# CommsBoard.net
KiCad netlist of a schematic drawn in EAGLE
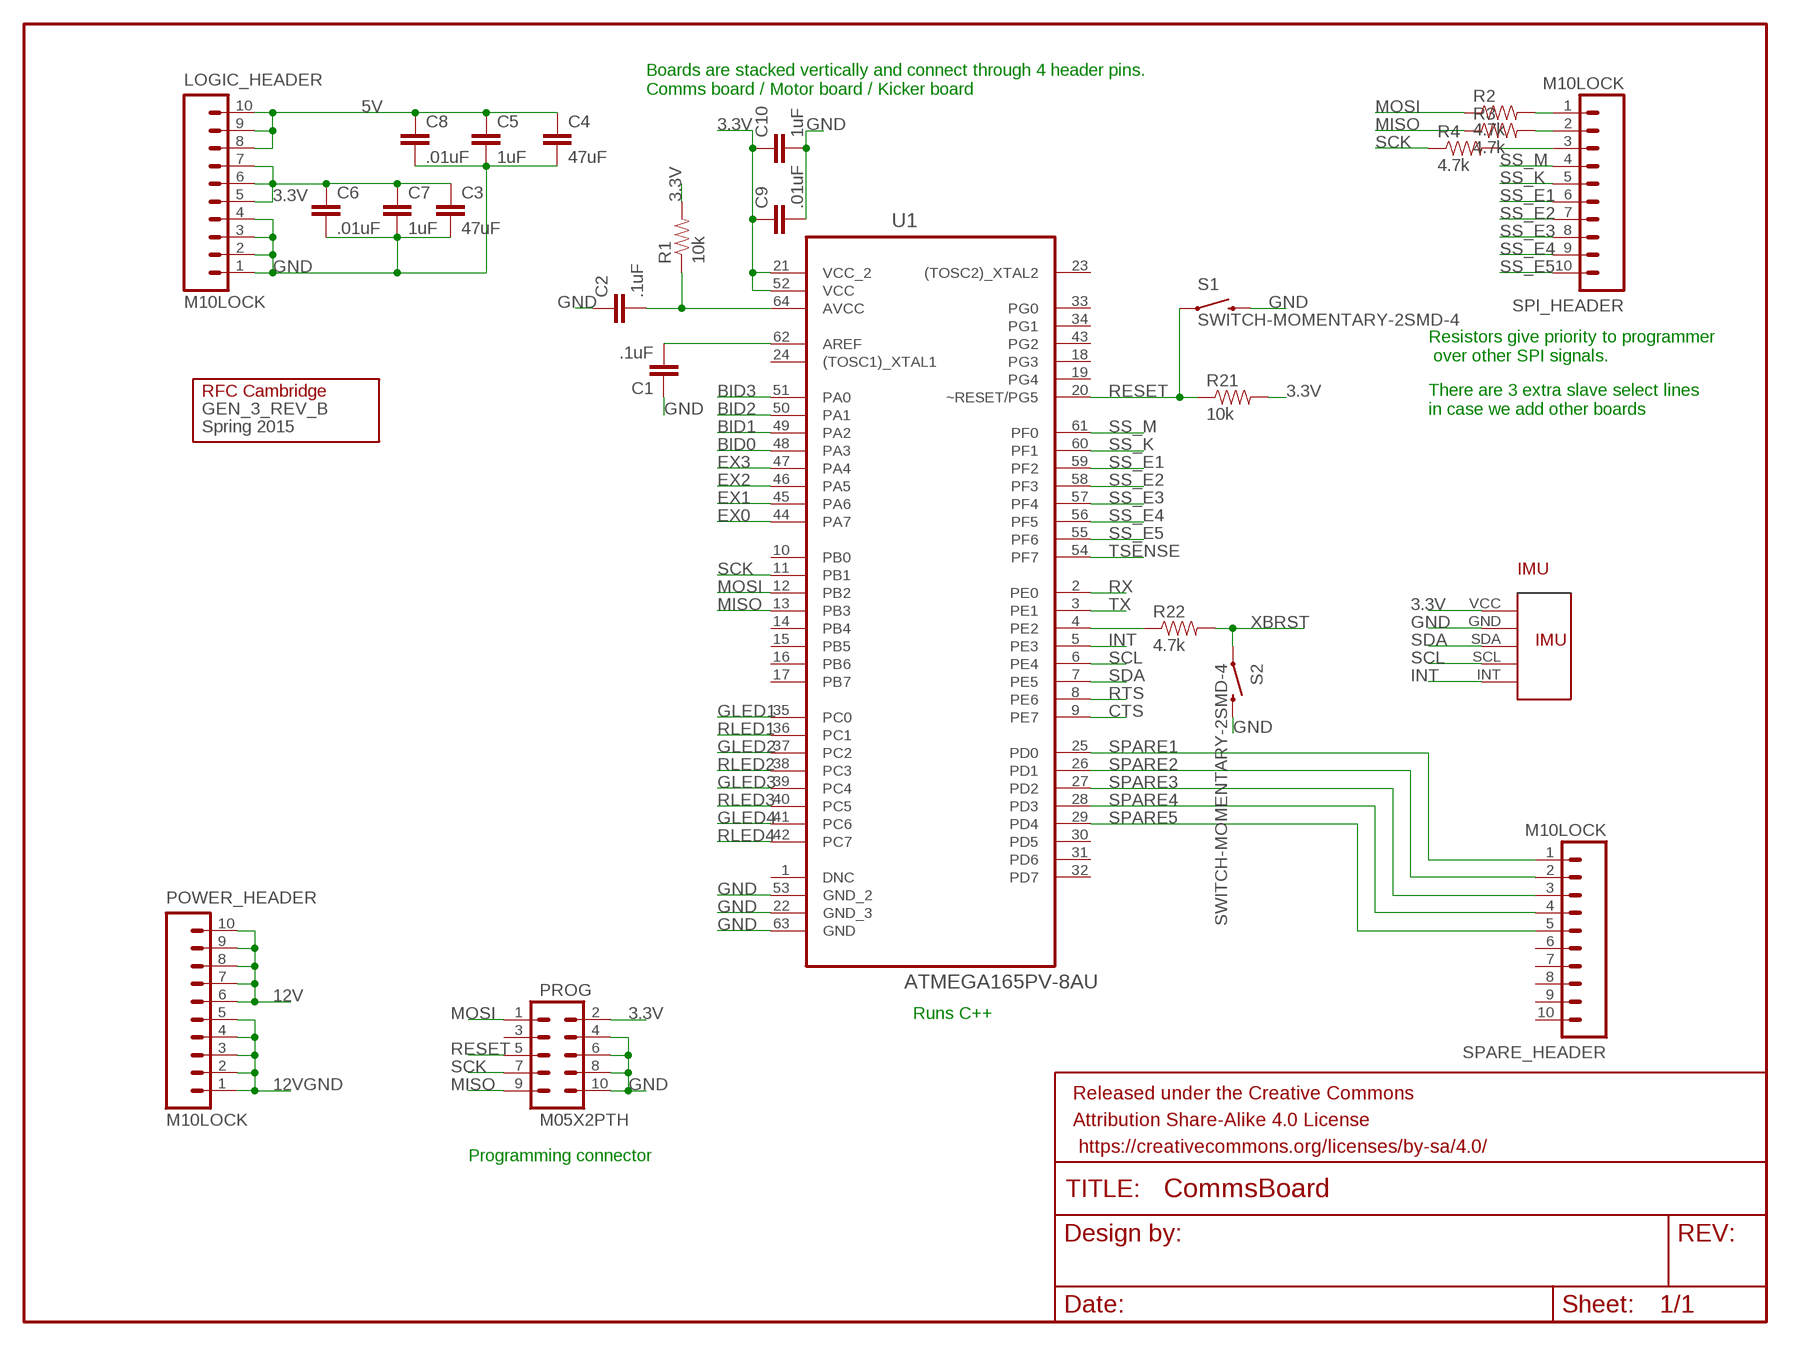
[diagram p0: schematic, sheet 1, part 1 of 2]
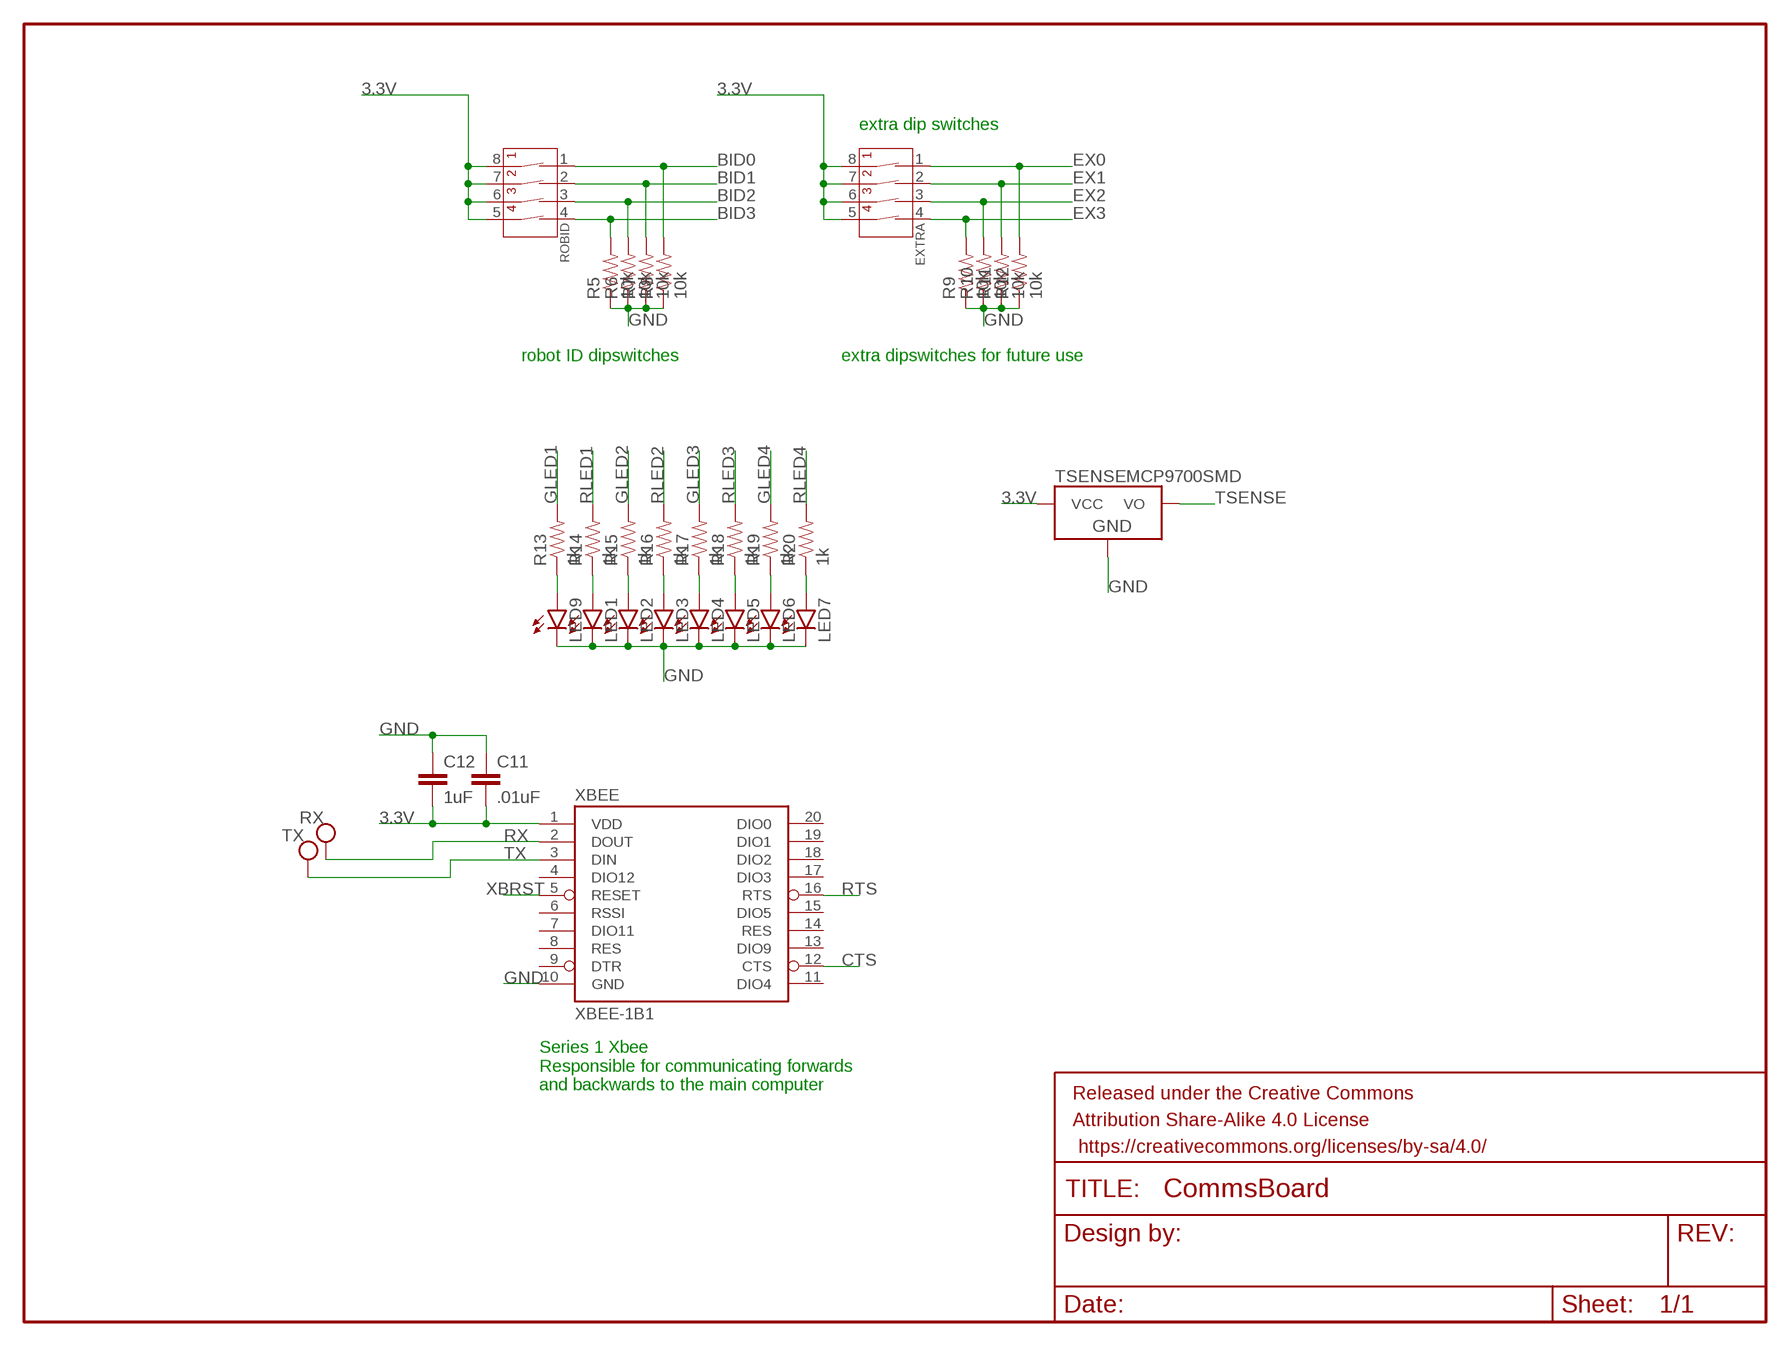
[diagram p1: schematic, sheet 1, part 2 of 2]

(export (version "E")
  (design (tool "Eeschema 10.0.6"))
  (components
    (comp (ref "C1")
      (value ".1uF")
      (footprint "eagle-import:0805")
      (libsource (lib "eagle-import") (part "CAP0805"))
    )
    (comp (ref "C2")
      (value ".1uF")
      (footprint "eagle-import:0805")
      (libsource (lib "eagle-import") (part "CAP0805"))
    )
    (comp (ref "C3")
      (value "47uF")
      (footprint "eagle-import:1206")
      (libsource (lib "eagle-import") (part "CAP1206"))
    )
    (comp (ref "C4")
      (value "47uF")
      (footprint "eagle-import:1206")
      (libsource (lib "eagle-import") (part "CAP1206"))
    )
    (comp (ref "C5")
      (value "1uF")
      (footprint "eagle-import:0805")
      (libsource (lib "eagle-import") (part "CAP0805"))
    )
    (comp (ref "C6")
      (value ".01uF")
      (footprint "eagle-import:0805")
      (libsource (lib "eagle-import") (part "CAP0805"))
    )
    (comp (ref "C7")
      (value "1uF")
      (footprint "eagle-import:0805")
      (libsource (lib "eagle-import") (part "CAP0805"))
    )
    (comp (ref "C8")
      (value ".01uF")
      (footprint "eagle-import:0805")
      (libsource (lib "eagle-import") (part "CAP0805"))
    )
    (comp (ref "C9")
      (value ".01uF")
      (footprint "eagle-import:0805")
      (libsource (lib "eagle-import") (part "CAP0805"))
    )
    (comp (ref "C10")
      (value "1uF")
      (footprint "eagle-import:0805")
      (libsource (lib "eagle-import") (part "CAP0805"))
    )
    (comp (ref "C11")
      (value ".01uF")
      (footprint "eagle-import:0805")
      (libsource (lib "eagle-import") (part "CAP0805"))
    )
    (comp (ref "C12")
      (value "1uF")
      (footprint "eagle-import:0805")
      (libsource (lib "eagle-import") (part "CAP0805"))
    )
    (comp (ref "EXTRA")
      (value "4-POS-DIP")
      (footprint "eagle-import:4-POS-DIP-SMD")
      (libsource (lib "eagle-import") (part "4-POS-DIP"))
    )
    (comp (ref "FRAME1")
      (value "FRAME-LETTER")
      (footprint "eagle-import:CREATIVE_COMMONS")
      (libsource (lib "eagle-import") (part "FRAME-LETTER"))
    )
    (comp (ref "FRAME2")
      (value "FRAME-LETTER")
      (footprint "eagle-import:CREATIVE_COMMONS")
      (libsource (lib "eagle-import") (part "FRAME-LETTER"))
    )
    (comp (ref "GEN_3_REV_B")
      (value "Spring 2015")
      (footprint "eagle-import:LOGO")
      (libsource (lib "eagle-import") (part "LOGO"))
    )
    (comp (ref "IMU")
      (value "MPU6050IMUMPU")
      (footprint "eagle-import:MPU-6050IMU")
      (libsource (lib "eagle-import") (part "MPU6050IMUMPU"))
    )
    (comp (ref "LED1")
      (value "LED1206")
      (footprint "eagle-import:LED-1206")
      (libsource (lib "eagle-import") (part "LED1206"))
    )
    (comp (ref "LED2")
      (value "LED1206")
      (footprint "eagle-import:LED-1206")
      (libsource (lib "eagle-import") (part "LED1206"))
    )
    (comp (ref "LED3")
      (value "LED1206")
      (footprint "eagle-import:LED-1206")
      (libsource (lib "eagle-import") (part "LED1206"))
    )
    (comp (ref "LED4")
      (value "LED1206")
      (footprint "eagle-import:LED-1206")
      (libsource (lib "eagle-import") (part "LED1206"))
    )
    (comp (ref "LED5")
      (value "LED1206")
      (footprint "eagle-import:LED-1206")
      (libsource (lib "eagle-import") (part "LED1206"))
    )
    (comp (ref "LED6")
      (value "LED1206")
      (footprint "eagle-import:LED-1206")
      (libsource (lib "eagle-import") (part "LED1206"))
    )
    (comp (ref "LED7")
      (value "LED1206")
      (footprint "eagle-import:LED-1206")
      (libsource (lib "eagle-import") (part "LED1206"))
    )
    (comp (ref "LED9")
      (value "LED1206")
      (footprint "eagle-import:LED-1206")
      (libsource (lib "eagle-import") (part "LED1206"))
    )
    (comp (ref "LOGIC_HEADER")
      (value "M10LOCK")
      (footprint "eagle-import:1X10_LOCK")
      (libsource (lib "eagle-import") (part "M10LOCK"))
    )
    (comp (ref "POWER_HEADER")
      (value "M10LOCK")
      (footprint "eagle-import:1X10_LOCK")
      (libsource (lib "eagle-import") (part "M10LOCK"))
    )
    (comp (ref "PROG")
      (value "M05X2PTH")
      (footprint "eagle-import:AVR_ICSP")
      (libsource (lib "eagle-import") (part "M05X2PTH"))
    )
    (comp (ref "R1")
      (value "10k")
      (footprint "eagle-import:0805")
      (libsource (lib "eagle-import") (part "RESISTOR0805-RES"))
    )
    (comp (ref "R2")
      (value "4.7k")
      (footprint "eagle-import:0805")
      (libsource (lib "eagle-import") (part "RESISTOR0805-RES"))
    )
    (comp (ref "R3")
      (value "4.7k")
      (footprint "eagle-import:0805")
      (libsource (lib "eagle-import") (part "RESISTOR0805-RES"))
    )
    (comp (ref "R4")
      (value "4.7k")
      (footprint "eagle-import:0805")
      (libsource (lib "eagle-import") (part "RESISTOR0805-RES"))
    )
    (comp (ref "R5")
      (value "10k")
      (footprint "eagle-import:0805")
      (libsource (lib "eagle-import") (part "RESISTOR0805-RES"))
    )
    (comp (ref "R6")
      (value "10k")
      (footprint "eagle-import:0805")
      (libsource (lib "eagle-import") (part "RESISTOR0805-RES"))
    )
    (comp (ref "R7")
      (value "10k")
      (footprint "eagle-import:0805")
      (libsource (lib "eagle-import") (part "RESISTOR0805-RES"))
    )
    (comp (ref "R8")
      (value "10k")
      (footprint "eagle-import:0805")
      (libsource (lib "eagle-import") (part "RESISTOR0805-RES"))
    )
    (comp (ref "R9")
      (value "10k")
      (footprint "eagle-import:0805")
      (libsource (lib "eagle-import") (part "RESISTOR0805-RES"))
    )
    (comp (ref "R10")
      (value "10k")
      (footprint "eagle-import:0805")
      (libsource (lib "eagle-import") (part "RESISTOR0805-RES"))
    )
    (comp (ref "R11")
      (value "10k")
      (footprint "eagle-import:0805")
      (libsource (lib "eagle-import") (part "RESISTOR0805-RES"))
    )
    (comp (ref "R12")
      (value "10k")
      (footprint "eagle-import:0805")
      (libsource (lib "eagle-import") (part "RESISTOR0805-RES"))
    )
    (comp (ref "R13")
      (value "1k")
      (footprint "eagle-import:0805")
      (libsource (lib "eagle-import") (part "RESISTOR0805-RES"))
    )
    (comp (ref "R14")
      (value "1k")
      (footprint "eagle-import:0805")
      (libsource (lib "eagle-import") (part "RESISTOR0805-RES"))
    )
    (comp (ref "R15")
      (value "1k")
      (footprint "eagle-import:0805")
      (libsource (lib "eagle-import") (part "RESISTOR0805-RES"))
    )
    (comp (ref "R16")
      (value "1k")
      (footprint "eagle-import:0805")
      (libsource (lib "eagle-import") (part "RESISTOR0805-RES"))
    )
    (comp (ref "R17")
      (value "1k")
      (footprint "eagle-import:0805")
      (libsource (lib "eagle-import") (part "RESISTOR0805-RES"))
    )
    (comp (ref "R18")
      (value "1k")
      (footprint "eagle-import:0805")
      (libsource (lib "eagle-import") (part "RESISTOR0805-RES"))
    )
    (comp (ref "R19")
      (value "1k")
      (footprint "eagle-import:0805")
      (libsource (lib "eagle-import") (part "RESISTOR0805-RES"))
    )
    (comp (ref "R20")
      (value "1k")
      (footprint "eagle-import:0805")
      (libsource (lib "eagle-import") (part "RESISTOR0805-RES"))
    )
    (comp (ref "R21")
      (value "10k")
      (footprint "eagle-import:0805")
      (libsource (lib "eagle-import") (part "RESISTOR0805-RES"))
    )
    (comp (ref "R22")
      (value "4.7k")
      (footprint "eagle-import:0805")
      (libsource (lib "eagle-import") (part "RESISTOR0805-RES"))
    )
    (comp (ref "ROBID")
      (value "4-POS-DIP")
      (footprint "eagle-import:4-POS-DIP-SMD")
      (libsource (lib "eagle-import") (part "4-POS-DIP"))
    )
    (comp (ref "RX")
      (value "TEST_PT")
      (footprint "eagle-import:TESTING_PT")
      (libsource (lib "eagle-import") (part "TEST_PT"))
    )
    (comp (ref "S1")
      (value "SWITCH-MOMENTARY-2SMD-4")
      (footprint "eagle-import:TACTILE_SWITCH_TALL")
      (libsource (lib "eagle-import") (part "SWITCH-MOMENTARY-2SMD-4"))
    )
    (comp (ref "S2")
      (value "SWITCH-MOMENTARY-2SMD-4")
      (footprint "eagle-import:TACTILE_SWITCH_TALL")
      (libsource (lib "eagle-import") (part "SWITCH-MOMENTARY-2SMD-4"))
    )
    (comp (ref "SPARE_HEADER")
      (value "M10LOCK")
      (footprint "eagle-import:1X10_LOCK")
      (libsource (lib "eagle-import") (part "M10LOCK"))
    )
    (comp (ref "SPI_HEADER")
      (value "M10LOCK")
      (footprint "eagle-import:1X10_LOCK")
      (libsource (lib "eagle-import") (part "M10LOCK"))
    )
    (comp (ref "TSENSE")
      (value "MCP9700SMD")
      (footprint "eagle-import:SOT23-3")
      (libsource (lib "eagle-import") (part "MCP9700SMD"))
    )
    (comp (ref "TX")
      (value "TEST_PT")
      (footprint "eagle-import:TESTING_PT")
      (libsource (lib "eagle-import") (part "TEST_PT"))
    )
    (comp (ref "U1")
      (value "ATMEGA165PV-8AU")
      (footprint "eagle-import:QFP80P1600X1600X120-64N")
      (libsource (lib "eagle-import") (part "ATMEGA165PV-8AU"))
    )
    (comp (ref "XBEE")
      (value "XBEE-1B1")
      (footprint "eagle-import:XBEE-1")
      (libsource (lib "eagle-import") (part "XBEE-1B1"))
    )
  )
  (nets
    (net (code "1") (name "/3.3V") (class "Default")
      (node (ref "C10") (pin "1") (pinfunction "1_1") (pintype "passive"))
      (node (ref "C11") (pin "2") (pinfunction "2_2") (pintype "passive"))
      (node (ref "C12") (pin "2") (pinfunction "2_2") (pintype "passive"))
      (node (ref "C3") (pin "1") (pinfunction "1_1") (pintype "passive"))
      (node (ref "C6") (pin "1") (pinfunction "1_1") (pintype "passive"))
      (node (ref "C7") (pin "1") (pinfunction "1_1") (pintype "passive"))
      (node (ref "C9") (pin "1") (pinfunction "1_1") (pintype "passive"))
      (node (ref "EXTRA") (pin "5") (pinfunction "4B_5") (pintype "bidirectional"))
      (node (ref "EXTRA") (pin "6") (pinfunction "3B_6") (pintype "bidirectional"))
      (node (ref "EXTRA") (pin "7") (pinfunction "2B_7") (pintype "bidirectional"))
      (node (ref "EXTRA") (pin "8") (pinfunction "1B_8") (pintype "bidirectional"))
      (node (ref "IMU") (pin "VCC") (pinfunction "VCC_VCC") (pintype "bidirectional"))
      (node (ref "LOGIC_HEADER") (pin "5") (pinfunction "5_5") (pintype "passive"))
      (node (ref "LOGIC_HEADER") (pin "6") (pinfunction "6_6") (pintype "passive"))
      (node (ref "LOGIC_HEADER") (pin "7") (pinfunction "7_7") (pintype "passive"))
      (node (ref "PROG") (pin "2") (pinfunction "2_2") (pintype "passive"))
      (node (ref "R1") (pin "2") (pinfunction "2_2") (pintype "passive"))
      (node (ref "R21") (pin "2") (pinfunction "2_2") (pintype "passive"))
      (node (ref "ROBID") (pin "5") (pinfunction "4B_5") (pintype "bidirectional"))
      (node (ref "ROBID") (pin "6") (pinfunction "3B_6") (pintype "bidirectional"))
      (node (ref "ROBID") (pin "7") (pinfunction "2B_7") (pintype "bidirectional"))
      (node (ref "ROBID") (pin "8") (pinfunction "1B_8") (pintype "bidirectional"))
      (node (ref "TSENSE") (pin "1") (pinfunction "VCC_1") (pintype "bidirectional"))
      (node (ref "U1") (pin "21") (pinfunction "VCC_2_21") (pintype "power_in"))
      (node (ref "U1") (pin "52") (pinfunction "VCC_52") (pintype "power_in"))
      (node (ref "XBEE") (pin "1") (pinfunction "VDD_1") (pintype "power_in"))
    )
    (net (code "2") (name "/5V") (class "Default")
      (node (ref "C4") (pin "1") (pinfunction "1_1") (pintype "passive"))
      (node (ref "C5") (pin "1") (pinfunction "1_1") (pintype "passive"))
      (node (ref "C8") (pin "1") (pinfunction "1_1") (pintype "passive"))
      (node (ref "LOGIC_HEADER") (pin "10") (pinfunction "10_10") (pintype "passive"))
      (node (ref "LOGIC_HEADER") (pin "8") (pinfunction "8_8") (pintype "passive"))
      (node (ref "LOGIC_HEADER") (pin "9") (pinfunction "9_9") (pintype "passive"))
    )
    (net (code "3") (name "/12V") (class "Default")
      (node (ref "POWER_HEADER") (pin "10") (pinfunction "10_10") (pintype "passive"))
      (node (ref "POWER_HEADER") (pin "6") (pinfunction "6_6") (pintype "passive"))
      (node (ref "POWER_HEADER") (pin "7") (pinfunction "7_7") (pintype "passive"))
      (node (ref "POWER_HEADER") (pin "8") (pinfunction "8_8") (pintype "passive"))
      (node (ref "POWER_HEADER") (pin "9") (pinfunction "9_9") (pintype "passive"))
    )
    (net (code "4") (name "/12VGND") (class "Default")
      (node (ref "POWER_HEADER") (pin "1") (pinfunction "1_1") (pintype "passive"))
      (node (ref "POWER_HEADER") (pin "2") (pinfunction "2_2") (pintype "passive"))
      (node (ref "POWER_HEADER") (pin "3") (pinfunction "3_3") (pintype "passive"))
      (node (ref "POWER_HEADER") (pin "4") (pinfunction "4_4") (pintype "passive"))
      (node (ref "POWER_HEADER") (pin "5") (pinfunction "5_5") (pintype "passive"))
    )
    (net (code "5") (name "/BID0") (class "Default")
      (node (ref "R8") (pin "2") (pinfunction "2_2") (pintype "passive"))
      (node (ref "ROBID") (pin "1") (pinfunction "1A_1") (pintype "bidirectional"))
      (node (ref "U1") (pin "48") (pinfunction "PA3_48") (pintype "bidirectional"))
    )
    (net (code "6") (name "/BID1") (class "Default")
      (node (ref "R7") (pin "2") (pinfunction "2_2") (pintype "passive"))
      (node (ref "ROBID") (pin "2") (pinfunction "2A_2") (pintype "bidirectional"))
      (node (ref "U1") (pin "49") (pinfunction "PA2_49") (pintype "bidirectional"))
    )
    (net (code "7") (name "/BID2") (class "Default")
      (node (ref "R6") (pin "2") (pinfunction "2_2") (pintype "passive"))
      (node (ref "ROBID") (pin "3") (pinfunction "3A_3") (pintype "bidirectional"))
      (node (ref "U1") (pin "50") (pinfunction "PA1_50") (pintype "bidirectional"))
    )
    (net (code "8") (name "/BID3") (class "Default")
      (node (ref "R5") (pin "2") (pinfunction "2_2") (pintype "passive"))
      (node (ref "ROBID") (pin "4") (pinfunction "4A_4") (pintype "bidirectional"))
      (node (ref "U1") (pin "51") (pinfunction "PA0_51") (pintype "bidirectional"))
    )
    (net (code "9") (name "/CTS") (class "Default")
      (node (ref "U1") (pin "9") (pinfunction "PE7_9") (pintype "bidirectional"))
      (node (ref "XBEE") (pin "12") (pinfunction "CTS_12") (pintype "output"))
    )
    (net (code "10") (name "/EX0") (class "Default")
      (node (ref "EXTRA") (pin "1") (pinfunction "1A_1") (pintype "bidirectional"))
      (node (ref "R12") (pin "2") (pinfunction "2_2") (pintype "passive"))
      (node (ref "U1") (pin "44") (pinfunction "PA7_44") (pintype "bidirectional"))
    )
    (net (code "11") (name "/EX1") (class "Default")
      (node (ref "EXTRA") (pin "2") (pinfunction "2A_2") (pintype "bidirectional"))
      (node (ref "R11") (pin "2") (pinfunction "2_2") (pintype "passive"))
      (node (ref "U1") (pin "45") (pinfunction "PA6_45") (pintype "bidirectional"))
    )
    (net (code "12") (name "/EX2") (class "Default")
      (node (ref "EXTRA") (pin "3") (pinfunction "3A_3") (pintype "bidirectional"))
      (node (ref "R10") (pin "2") (pinfunction "2_2") (pintype "passive"))
      (node (ref "U1") (pin "46") (pinfunction "PA5_46") (pintype "bidirectional"))
    )
    (net (code "13") (name "/EX3") (class "Default")
      (node (ref "EXTRA") (pin "4") (pinfunction "4A_4") (pintype "bidirectional"))
      (node (ref "R9") (pin "2") (pinfunction "2_2") (pintype "passive"))
      (node (ref "U1") (pin "47") (pinfunction "PA4_47") (pintype "bidirectional"))
    )
    (net (code "14") (name "/GLED1") (class "Default")
      (node (ref "R13") (pin "2") (pinfunction "2_2") (pintype "passive"))
      (node (ref "U1") (pin "35") (pinfunction "PC0_35") (pintype "bidirectional"))
    )
    (net (code "15") (name "/GLED2") (class "Default")
      (node (ref "R15") (pin "2") (pinfunction "2_2") (pintype "passive"))
      (node (ref "U1") (pin "37") (pinfunction "PC2_37") (pintype "bidirectional"))
    )
    (net (code "16") (name "/GLED3") (class "Default")
      (node (ref "R17") (pin "2") (pinfunction "2_2") (pintype "passive"))
      (node (ref "U1") (pin "39") (pinfunction "PC4_39") (pintype "bidirectional"))
    )
    (net (code "17") (name "/GLED4") (class "Default")
      (node (ref "R19") (pin "2") (pinfunction "2_2") (pintype "passive"))
      (node (ref "U1") (pin "41") (pinfunction "PC6_41") (pintype "bidirectional"))
    )
    (net (code "18") (name "/GND") (class "Default")
      (node (ref "C1") (pin "1") (pinfunction "1_1") (pintype "passive"))
      (node (ref "C10") (pin "2") (pinfunction "2_2") (pintype "passive"))
      (node (ref "C11") (pin "1") (pinfunction "1_1") (pintype "passive"))
      (node (ref "C12") (pin "1") (pinfunction "1_1") (pintype "passive"))
      (node (ref "C2") (pin "1") (pinfunction "1_1") (pintype "passive"))
      (node (ref "C3") (pin "2") (pinfunction "2_2") (pintype "passive"))
      (node (ref "C4") (pin "2") (pinfunction "2_2") (pintype "passive"))
      (node (ref "C5") (pin "2") (pinfunction "2_2") (pintype "passive"))
      (node (ref "C6") (pin "2") (pinfunction "2_2") (pintype "passive"))
      (node (ref "C7") (pin "2") (pinfunction "2_2") (pintype "passive"))
      (node (ref "C8") (pin "2") (pinfunction "2_2") (pintype "passive"))
      (node (ref "C9") (pin "2") (pinfunction "2_2") (pintype "passive"))
      (node (ref "IMU") (pin "GND") (pinfunction "GND_GND") (pintype "bidirectional"))
      (node (ref "LED1") (pin "C") (pinfunction "C_C") (pintype "passive"))
      (node (ref "LED2") (pin "C") (pinfunction "C_C") (pintype "passive"))
      (node (ref "LED3") (pin "C") (pinfunction "C_C") (pintype "passive"))
      (node (ref "LED4") (pin "C") (pinfunction "C_C") (pintype "passive"))
      (node (ref "LED5") (pin "C") (pinfunction "C_C") (pintype "passive"))
      (node (ref "LED6") (pin "C") (pinfunction "C_C") (pintype "passive"))
      (node (ref "LED7") (pin "C") (pinfunction "C_C") (pintype "passive"))
      (node (ref "LED9") (pin "C") (pinfunction "C_C") (pintype "passive"))
      (node (ref "LOGIC_HEADER") (pin "1") (pinfunction "1_1") (pintype "passive"))
      (node (ref "LOGIC_HEADER") (pin "2") (pinfunction "2_2") (pintype "passive"))
      (node (ref "LOGIC_HEADER") (pin "3") (pinfunction "3_3") (pintype "passive"))
      (node (ref "LOGIC_HEADER") (pin "4") (pinfunction "4_4") (pintype "passive"))
      (node (ref "PROG") (pin "10") (pinfunction "10_10") (pintype "passive"))
      (node (ref "PROG") (pin "4") (pinfunction "4_4") (pintype "passive"))
      (node (ref "PROG") (pin "6") (pinfunction "6_6") (pintype "passive"))
      (node (ref "PROG") (pin "8") (pinfunction "8_8") (pintype "passive"))
      (node (ref "R10") (pin "1") (pinfunction "1_1") (pintype "passive"))
      (node (ref "R11") (pin "1") (pinfunction "1_1") (pintype "passive"))
      (node (ref "R12") (pin "1") (pinfunction "1_1") (pintype "passive"))
      (node (ref "R5") (pin "1") (pinfunction "1_1") (pintype "passive"))
      (node (ref "R6") (pin "1") (pinfunction "1_1") (pintype "passive"))
      (node (ref "R7") (pin "1") (pinfunction "1_1") (pintype "passive"))
      (node (ref "R8") (pin "1") (pinfunction "1_1") (pintype "passive"))
      (node (ref "R9") (pin "1") (pinfunction "1_1") (pintype "passive"))
      (node (ref "S1") (pin "B2") (pinfunction "2_B2") (pintype "passive"))
      (node (ref "S2") (pin "B2") (pinfunction "2_B2") (pintype "passive"))
      (node (ref "TSENSE") (pin "3") (pinfunction "GND_3") (pintype "bidirectional"))
      (node (ref "U1") (pin "22") (pinfunction "GND_3_22") (pintype "passive"))
      (node (ref "U1") (pin "53") (pinfunction "GND_2_53") (pintype "passive"))
      (node (ref "U1") (pin "63") (pinfunction "GND_63") (pintype "passive"))
      (node (ref "XBEE") (pin "10") (pinfunction "GND_10") (pintype "power_in"))
    )
    (net (code "19") (name "/INT") (class "Default")
      (node (ref "IMU") (pin "INT") (pinfunction "INT_INT") (pintype "bidirectional"))
      (node (ref "U1") (pin "5") (pinfunction "PE3_5") (pintype "bidirectional"))
    )
    (net (code "20") (name "/MISO") (class "Default")
      (node (ref "PROG") (pin "9") (pinfunction "9_9") (pintype "passive"))
      (node (ref "R3") (pin "1") (pinfunction "1_1") (pintype "passive"))
      (node (ref "U1") (pin "13") (pinfunction "PB3_13") (pintype "bidirectional"))
    )
    (net (code "21") (name "/MOSI") (class "Default")
      (node (ref "PROG") (pin "1") (pinfunction "1_1") (pintype "passive"))
      (node (ref "R2") (pin "1") (pinfunction "1_1") (pintype "passive"))
      (node (ref "U1") (pin "12") (pinfunction "PB2_12") (pintype "bidirectional"))
    )
    (net (code "22") (name "/RESET") (class "Default")
      (node (ref "PROG") (pin "5") (pinfunction "5_5") (pintype "passive"))
      (node (ref "R21") (pin "1") (pinfunction "1_1") (pintype "passive"))
      (node (ref "S1") (pin "A2") (pinfunction "1_A2") (pintype "passive"))
      (node (ref "U1") (pin "20") (pinfunction "~{RESET/PG5}_20") (pintype "bidirectional"))
    )
    (net (code "23") (name "/RLED1") (class "Default")
      (node (ref "R14") (pin "2") (pinfunction "2_2") (pintype "passive"))
      (node (ref "U1") (pin "36") (pinfunction "PC1_36") (pintype "bidirectional"))
    )
    (net (code "24") (name "/RLED2") (class "Default")
      (node (ref "R16") (pin "2") (pinfunction "2_2") (pintype "passive"))
      (node (ref "U1") (pin "38") (pinfunction "PC3_38") (pintype "bidirectional"))
    )
    (net (code "25") (name "/RLED3") (class "Default")
      (node (ref "R18") (pin "2") (pinfunction "2_2") (pintype "passive"))
      (node (ref "U1") (pin "40") (pinfunction "PC5_40") (pintype "bidirectional"))
    )
    (net (code "26") (name "/RLED4") (class "Default")
      (node (ref "R20") (pin "2") (pinfunction "2_2") (pintype "passive"))
      (node (ref "U1") (pin "42") (pinfunction "PC7_42") (pintype "bidirectional"))
    )
    (net (code "27") (name "/RTS") (class "Default")
      (node (ref "U1") (pin "8") (pinfunction "PE6_8") (pintype "bidirectional"))
      (node (ref "XBEE") (pin "16") (pinfunction "RTS_16") (pintype "input"))
    )
    (net (code "28") (name "/RX") (class "Default")
      (node (ref "RX") (pin "P$1") (pinfunction "P$1_P$1") (pintype "bidirectional"))
      (node (ref "U1") (pin "2") (pinfunction "PE0_2") (pintype "bidirectional"))
      (node (ref "XBEE") (pin "2") (pinfunction "DOUT_2") (pintype "output"))
    )
    (net (code "29") (name "/SCK") (class "Default")
      (node (ref "PROG") (pin "7") (pinfunction "7_7") (pintype "passive"))
      (node (ref "R4") (pin "1") (pinfunction "1_1") (pintype "passive"))
      (node (ref "U1") (pin "11") (pinfunction "PB1_11") (pintype "bidirectional"))
    )
    (net (code "30") (name "/SCL") (class "Default")
      (node (ref "IMU") (pin "SCL") (pinfunction "SCL_SCL") (pintype "bidirectional"))
      (node (ref "U1") (pin "6") (pinfunction "PE4_6") (pintype "bidirectional"))
    )
    (net (code "31") (name "/SDA") (class "Default")
      (node (ref "IMU") (pin "SDA") (pinfunction "SDA_SDA") (pintype "bidirectional"))
      (node (ref "U1") (pin "7") (pinfunction "PE5_7") (pintype "bidirectional"))
    )
    (net (code "32") (name "/SPARE1") (class "Default")
      (node (ref "SPARE_HEADER") (pin "1") (pinfunction "1_1") (pintype "passive"))
      (node (ref "U1") (pin "25") (pinfunction "PD0_25") (pintype "bidirectional"))
    )
    (net (code "33") (name "/SPARE2") (class "Default")
      (node (ref "SPARE_HEADER") (pin "2") (pinfunction "2_2") (pintype "passive"))
      (node (ref "U1") (pin "26") (pinfunction "PD1_26") (pintype "bidirectional"))
    )
    (net (code "34") (name "/SPARE3") (class "Default")
      (node (ref "SPARE_HEADER") (pin "3") (pinfunction "3_3") (pintype "passive"))
      (node (ref "U1") (pin "27") (pinfunction "PD2_27") (pintype "bidirectional"))
    )
    (net (code "35") (name "/SPARE4") (class "Default")
      (node (ref "SPARE_HEADER") (pin "4") (pinfunction "4_4") (pintype "passive"))
      (node (ref "U1") (pin "28") (pinfunction "PD3_28") (pintype "bidirectional"))
    )
    (net (code "36") (name "/SPARE5") (class "Default")
      (node (ref "SPARE_HEADER") (pin "5") (pinfunction "5_5") (pintype "passive"))
      (node (ref "U1") (pin "29") (pinfunction "PD4_29") (pintype "bidirectional"))
    )
    (net (code "37") (name "/SS_E1") (class "Default")
      (node (ref "SPI_HEADER") (pin "6") (pinfunction "6_6") (pintype "passive"))
      (node (ref "U1") (pin "59") (pinfunction "PF2_59") (pintype "bidirectional"))
    )
    (net (code "38") (name "/SS_E2") (class "Default")
      (node (ref "SPI_HEADER") (pin "7") (pinfunction "7_7") (pintype "passive"))
      (node (ref "U1") (pin "58") (pinfunction "PF3_58") (pintype "bidirectional"))
    )
    (net (code "39") (name "/SS_E3") (class "Default")
      (node (ref "SPI_HEADER") (pin "8") (pinfunction "8_8") (pintype "passive"))
      (node (ref "U1") (pin "57") (pinfunction "PF4_57") (pintype "bidirectional"))
    )
    (net (code "40") (name "/SS_E4") (class "Default")
      (node (ref "SPI_HEADER") (pin "9") (pinfunction "9_9") (pintype "passive"))
      (node (ref "U1") (pin "56") (pinfunction "PF5_56") (pintype "bidirectional"))
    )
    (net (code "41") (name "/SS_E5") (class "Default")
      (node (ref "SPI_HEADER") (pin "10") (pinfunction "10_10") (pintype "passive"))
      (node (ref "U1") (pin "55") (pinfunction "PF6_55") (pintype "bidirectional"))
    )
    (net (code "42") (name "/SS_K") (class "Default")
      (node (ref "SPI_HEADER") (pin "5") (pinfunction "5_5") (pintype "passive"))
      (node (ref "U1") (pin "60") (pinfunction "PF1_60") (pintype "bidirectional"))
    )
    (net (code "43") (name "/SS_M") (class "Default")
      (node (ref "SPI_HEADER") (pin "4") (pinfunction "4_4") (pintype "passive"))
      (node (ref "U1") (pin "61") (pinfunction "PF0_61") (pintype "bidirectional"))
    )
    (net (code "44") (name "/TSENSE") (class "Default")
      (node (ref "TSENSE") (pin "2") (pinfunction "VO_2") (pintype "bidirectional"))
      (node (ref "U1") (pin "54") (pinfunction "PF7_54") (pintype "bidirectional"))
    )
    (net (code "45") (name "/TX") (class "Default")
      (node (ref "TX") (pin "P$1") (pinfunction "P$1_P$1") (pintype "bidirectional"))
      (node (ref "U1") (pin "3") (pinfunction "PE1_3") (pintype "bidirectional"))
      (node (ref "XBEE") (pin "3") (pinfunction "DIN_3") (pintype "input"))
    )
    (net (code "46") (name "/XBRST") (class "Default")
      (node (ref "R22") (pin "2") (pinfunction "2_2") (pintype "passive"))
      (node (ref "S2") (pin "A2") (pinfunction "1_A2") (pintype "passive"))
      (node (ref "XBEE") (pin "5") (pinfunction "RESET_5") (pintype "input"))
    )
    (net (code "47") (name "Net-(LED1-PadA)") (class "Default")
      (node (ref "LED1") (pin "A") (pinfunction "A_A") (pintype "passive"))
      (node (ref "R14") (pin "1") (pinfunction "1_1") (pintype "passive"))
    )
    (net (code "48") (name "Net-(LED2-PadA)") (class "Default")
      (node (ref "LED2") (pin "A") (pinfunction "A_A") (pintype "passive"))
      (node (ref "R15") (pin "1") (pinfunction "1_1") (pintype "passive"))
    )
    (net (code "49") (name "Net-(LED3-PadA)") (class "Default")
      (node (ref "LED3") (pin "A") (pinfunction "A_A") (pintype "passive"))
      (node (ref "R16") (pin "1") (pinfunction "1_1") (pintype "passive"))
    )
    (net (code "50") (name "Net-(LED4-PadA)") (class "Default")
      (node (ref "LED4") (pin "A") (pinfunction "A_A") (pintype "passive"))
      (node (ref "R17") (pin "1") (pinfunction "1_1") (pintype "passive"))
    )
    (net (code "51") (name "Net-(LED5-PadA)") (class "Default")
      (node (ref "LED5") (pin "A") (pinfunction "A_A") (pintype "passive"))
      (node (ref "R18") (pin "1") (pinfunction "1_1") (pintype "passive"))
    )
    (net (code "52") (name "Net-(LED6-PadA)") (class "Default")
      (node (ref "LED6") (pin "A") (pinfunction "A_A") (pintype "passive"))
      (node (ref "R19") (pin "1") (pinfunction "1_1") (pintype "passive"))
    )
    (net (code "53") (name "Net-(LED7-PadA)") (class "Default")
      (node (ref "LED7") (pin "A") (pinfunction "A_A") (pintype "passive"))
      (node (ref "R20") (pin "1") (pinfunction "1_1") (pintype "passive"))
    )
    (net (code "54") (name "Net-(LED9-PadA)") (class "Default")
      (node (ref "LED9") (pin "A") (pinfunction "A_A") (pintype "passive"))
      (node (ref "R13") (pin "1") (pinfunction "1_1") (pintype "passive"))
    )
    (net (code "55") (name "Net-(R2-Pad2)") (class "Default")
      (node (ref "R2") (pin "2") (pinfunction "2_2") (pintype "passive"))
      (node (ref "SPI_HEADER") (pin "1") (pinfunction "1_1") (pintype "passive"))
    )
    (net (code "56") (name "Net-(R3-Pad2)") (class "Default")
      (node (ref "R3") (pin "2") (pinfunction "2_2") (pintype "passive"))
      (node (ref "SPI_HEADER") (pin "2") (pinfunction "2_2") (pintype "passive"))
    )
    (net (code "57") (name "Net-(R4-Pad2)") (class "Default")
      (node (ref "R4") (pin "2") (pinfunction "2_2") (pintype "passive"))
      (node (ref "SPI_HEADER") (pin "3") (pinfunction "3_3") (pintype "passive"))
    )
    (net (code "58") (name "Net-(U1-AREF)") (class "Default")
      (node (ref "C1") (pin "2") (pinfunction "2_2") (pintype "passive"))
      (node (ref "U1") (pin "62") (pinfunction "AREF_62") (pintype "input"))
    )
    (net (code "59") (name "Net-(U1-AVCC)") (class "Default")
      (node (ref "C2") (pin "2") (pinfunction "2_2") (pintype "passive"))
      (node (ref "R1") (pin "1") (pinfunction "1_1") (pintype "passive"))
      (node (ref "U1") (pin "64") (pinfunction "AVCC_64") (pintype "power_in"))
    )
    (net (code "60") (name "Net-(U1-PE2)") (class "Default")
      (node (ref "R22") (pin "1") (pinfunction "1_1") (pintype "passive"))
      (node (ref "U1") (pin "4") (pinfunction "PE2_4") (pintype "bidirectional"))
    )
    (net (code "61") (name "unconnected-(PROG-Pad3)") (class "Default")
      (node (ref "PROG") (pin "3") (pinfunction "3_3") (pintype "passive"))
    )
    (net (code "62") (name "unconnected-(SPARE_HEADER-Pad6)") (class "Default")
      (node (ref "SPARE_HEADER") (pin "6") (pinfunction "6_6") (pintype "passive"))
    )
    (net (code "63") (name "unconnected-(SPARE_HEADER-Pad7)") (class "Default")
      (node (ref "SPARE_HEADER") (pin "7") (pinfunction "7_7") (pintype "passive"))
    )
    (net (code "64") (name "unconnected-(SPARE_HEADER-Pad8)") (class "Default")
      (node (ref "SPARE_HEADER") (pin "8") (pinfunction "8_8") (pintype "passive"))
    )
    (net (code "65") (name "unconnected-(SPARE_HEADER-Pad9)") (class "Default")
      (node (ref "SPARE_HEADER") (pin "9") (pinfunction "9_9") (pintype "passive"))
    )
    (net (code "66") (name "unconnected-(SPARE_HEADER-Pad10)") (class "Default")
      (node (ref "SPARE_HEADER") (pin "10") (pinfunction "10_10") (pintype "passive"))
    )
    (net (code "67") (name "unconnected-(U1-(TOSC1)_XTAL1-Pad24)") (class "Default")
      (node (ref "U1") (pin "24") (pinfunction "(TOSC1)_XTAL1_24") (pintype "input"))
    )
    (net (code "68") (name "unconnected-(U1-(TOSC2)_XTAL2-Pad23)") (class "Default")
      (node (ref "U1") (pin "23") (pinfunction "(TOSC2)_XTAL2_23") (pintype "output"))
    )
    (net (code "69") (name "unconnected-(U1-DNC-Pad1)") (class "Default")
      (node (ref "U1") (pin "1") (pinfunction "DNC_1") (pintype "no_connect"))
    )
    (net (code "70") (name "unconnected-(U1-PB0-Pad10)") (class "Default")
      (node (ref "U1") (pin "10") (pinfunction "PB0_10") (pintype "bidirectional"))
    )
    (net (code "71") (name "unconnected-(U1-PB4-Pad14)") (class "Default")
      (node (ref "U1") (pin "14") (pinfunction "PB4_14") (pintype "bidirectional"))
    )
    (net (code "72") (name "unconnected-(U1-PB5-Pad15)") (class "Default")
      (node (ref "U1") (pin "15") (pinfunction "PB5_15") (pintype "bidirectional"))
    )
    (net (code "73") (name "unconnected-(U1-PB6-Pad16)") (class "Default")
      (node (ref "U1") (pin "16") (pinfunction "PB6_16") (pintype "bidirectional"))
    )
    (net (code "74") (name "unconnected-(U1-PB7-Pad17)") (class "Default")
      (node (ref "U1") (pin "17") (pinfunction "PB7_17") (pintype "bidirectional"))
    )
    (net (code "75") (name "unconnected-(U1-PD5-Pad30)") (class "Default")
      (node (ref "U1") (pin "30") (pinfunction "PD5_30") (pintype "bidirectional"))
    )
    (net (code "76") (name "unconnected-(U1-PD6-Pad31)") (class "Default")
      (node (ref "U1") (pin "31") (pinfunction "PD6_31") (pintype "bidirectional"))
    )
    (net (code "77") (name "unconnected-(U1-PD7-Pad32)") (class "Default")
      (node (ref "U1") (pin "32") (pinfunction "PD7_32") (pintype "bidirectional"))
    )
    (net (code "78") (name "unconnected-(U1-PG0-Pad33)") (class "Default")
      (node (ref "U1") (pin "33") (pinfunction "PG0_33") (pintype "bidirectional"))
    )
    (net (code "79") (name "unconnected-(U1-PG1-Pad34)") (class "Default")
      (node (ref "U1") (pin "34") (pinfunction "PG1_34") (pintype "bidirectional"))
    )
    (net (code "80") (name "unconnected-(U1-PG2-Pad43)") (class "Default")
      (node (ref "U1") (pin "43") (pinfunction "PG2_43") (pintype "bidirectional"))
    )
    (net (code "81") (name "unconnected-(U1-PG3-Pad18)") (class "Default")
      (node (ref "U1") (pin "18") (pinfunction "PG3_18") (pintype "bidirectional"))
    )
    (net (code "82") (name "unconnected-(U1-PG4-Pad19)") (class "Default")
      (node (ref "U1") (pin "19") (pinfunction "PG4_19") (pintype "bidirectional"))
    )
    (net (code "83") (name "unconnected-(XBEE-DIO0-Pad20)") (class "Default")
      (node (ref "XBEE") (pin "20") (pinfunction "DIO0_20") (pintype "bidirectional"))
    )
    (net (code "84") (name "unconnected-(XBEE-DIO1-Pad19)") (class "Default")
      (node (ref "XBEE") (pin "19") (pinfunction "DIO1_19") (pintype "bidirectional"))
    )
    (net (code "85") (name "unconnected-(XBEE-DIO2-Pad18)") (class "Default")
      (node (ref "XBEE") (pin "18") (pinfunction "DIO2_18") (pintype "bidirectional"))
    )
    (net (code "86") (name "unconnected-(XBEE-DIO3-Pad17)") (class "Default")
      (node (ref "XBEE") (pin "17") (pinfunction "DIO3_17") (pintype "bidirectional"))
    )
    (net (code "87") (name "unconnected-(XBEE-DIO4-Pad11)") (class "Default")
      (node (ref "XBEE") (pin "11") (pinfunction "DIO4_11") (pintype "bidirectional"))
    )
    (net (code "88") (name "unconnected-(XBEE-DIO5-Pad15)") (class "Default")
      (node (ref "XBEE") (pin "15") (pinfunction "DIO5_15") (pintype "bidirectional"))
    )
    (net (code "89") (name "unconnected-(XBEE-DIO9-Pad13)") (class "Default")
      (node (ref "XBEE") (pin "13") (pinfunction "DIO9_13") (pintype "bidirectional"))
    )
    (net (code "90") (name "unconnected-(XBEE-DIO11-Pad7)") (class "Default")
      (node (ref "XBEE") (pin "7") (pinfunction "DIO11_7") (pintype "bidirectional"))
    )
    (net (code "91") (name "unconnected-(XBEE-DIO12-Pad4)") (class "Default")
      (node (ref "XBEE") (pin "4") (pinfunction "DIO12_4") (pintype "bidirectional"))
    )
    (net (code "92") (name "unconnected-(XBEE-DTR-Pad9)") (class "Default")
      (node (ref "XBEE") (pin "9") (pinfunction "DTR_9") (pintype "bidirectional"))
    )
    (net (code "93") (name "unconnected-(XBEE-RES-Pad8)") (class "Default")
      (node (ref "XBEE") (pin "8") (pinfunction "RES_8") (pintype "bidirectional"))
    )
    (net (code "94") (name "unconnected-(XBEE-RES-Pad14)") (class "Default")
      (node (ref "XBEE") (pin "14") (pinfunction "RES_14") (pintype "bidirectional"))
    )
    (net (code "95") (name "unconnected-(XBEE-RSSI-Pad6)") (class "Default")
      (node (ref "XBEE") (pin "6") (pinfunction "RSSI_6") (pintype "bidirectional"))
    )
  )
)
